# LCL.net
KiCad netlist of a schematic drawn in Altium Designer
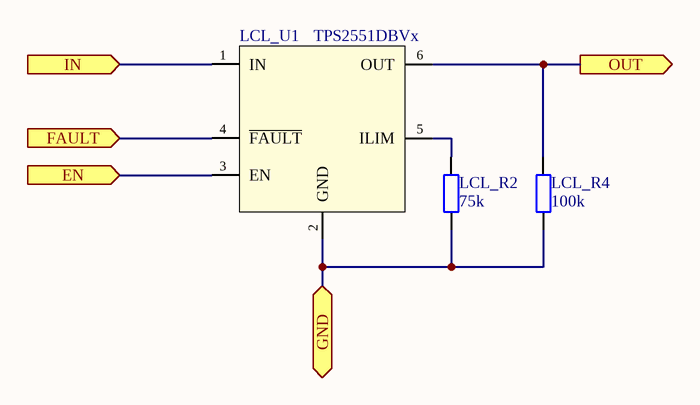
[diagram p0: LCL.SchDoc]

(export (version "E")
  (design (tool "Eeschema 10.0.6"))
  (components
    (comp (ref "LCL_R2")
      (value "75k")
      (footprint "SMD_Resistor_0603")
      (libsource (lib "resistors") (part "Res"))
    )
    (comp (ref "LCL_R4")
      (value "100k")
      (footprint "SMD_Resistor_0603")
      (libsource (lib "resistors") (part "Res"))
    )
    (comp (ref "LCL_U1")
      (value "TPS2551DBVx")
      (footprint "SOT23-6")
      (description "Adjustable Current-Limited Power-Distribution Switch.")
      (fields (field (name "MANUFACTURER") "Texas Instruments"))
      (libsource (lib "microcircuits") (part "TPS2551DBVx"))
    )
  )
  (nets
    (net (code "1") (name "/EN") (class "Default")
      (node (ref "LCL_U1") (pin "3") (pinfunction "EN_3") (pintype "passive"))
    )
    (net (code "2") (name "/FAULT") (class "Default")
      (node (ref "LCL_U1") (pin "4") (pinfunction "~{FAULT}_4") (pintype "passive"))
    )
    (net (code "3") (name "/GND") (class "Default")
      (node (ref "LCL_R2") (pin "1") (pinfunction "1_1") (pintype "passive"))
      (node (ref "LCL_R4") (pin "1") (pinfunction "1_1") (pintype "passive"))
      (node (ref "LCL_U1") (pin "2") (pinfunction "GND_2") (pintype "passive"))
    )
    (net (code "4") (name "/IN") (class "Default")
      (node (ref "LCL_U1") (pin "1") (pinfunction "IN_1") (pintype "passive"))
    )
    (net (code "5") (name "/OUT") (class "Default")
      (node (ref "LCL_R4") (pin "2") (pinfunction "2_2") (pintype "passive"))
      (node (ref "LCL_U1") (pin "6") (pinfunction "OUT_6") (pintype "passive"))
    )
    (net (code "6") (name "Net-(LCL_U1-ILIM)") (class "Default")
      (node (ref "LCL_R2") (pin "2") (pinfunction "2_2") (pintype "passive"))
      (node (ref "LCL_U1") (pin "5") (pinfunction "ILIM_5") (pintype "passive"))
    )
  )
)
